# Interface.net
KiCad netlist of a schematic drawn in Altium Designer
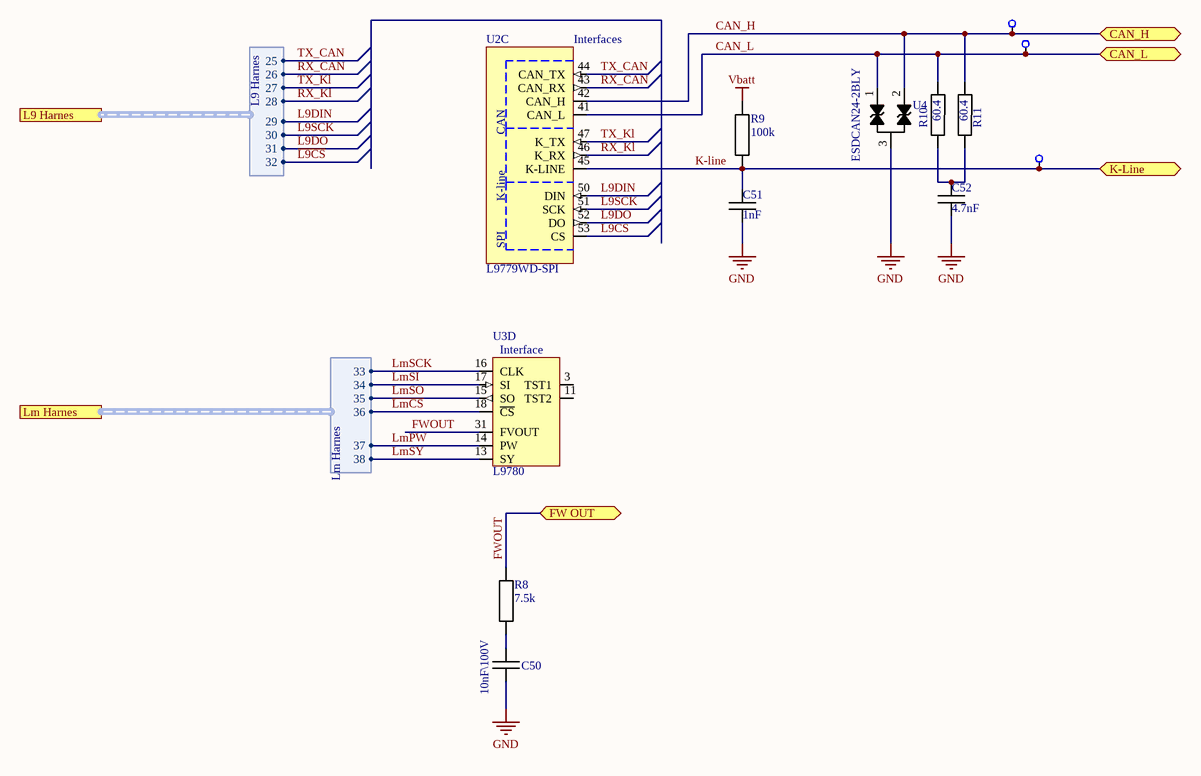
[diagram p0: Interface.SchDoc]

(export (version "E")
  (design (tool "Eeschema 10.0.6"))
  (components
    (comp (ref "C50")
      (value "10n~{F}100V")
      (footprint "SMD 0603")
      (description "CC0603KRX7R0BB103")
      (libsource (lib "Maks_lib") (part "Capasitor"))
    )
    (comp (ref "C51")
      (value "1nF")
      (footprint "SMD 0603")
      (description "CC0603KRX7R9BB102")
      (libsource (lib "Maks_lib") (part "Capasitor"))
    )
    (comp (ref "C52")
      (value "4.7nF")
      (footprint "SMD 0603")
      (description "CC0603KRX7R9BB472")
      (libsource (lib "Maks_lib") (part "Capasitor"))
    )
    (comp (ref "R8")
      (value "7.5k")
      (footprint "SMD 0603")
      (description "RC0603FR-077K5L")
      (libsource (lib "") (part "Resistor_1"))
    )
    (comp (ref "R9")
      (value "100k")
      (footprint "SMD 0603")
      (description "RT0603BRD07100KL")
      (libsource (lib "Maks_lib") (part "Resistor"))
    )
    (comp (ref "R10")
      (value "60.4")
      (footprint "SMD 0603")
      (description "RC0603FR-0760R4L")
      (libsource (lib "Maks_lib") (part "Resistor"))
    )
    (comp (ref "R11")
      (value "60.4")
      (footprint "SMD 0603")
      (description "RC0603FR-0760R4L")
      (libsource (lib "Maks_lib") (part "Resistor"))
    )
    (comp (ref "TP31")
      (value "TestPoint")
      (footprint "TESTPOINT")
      (description "testPoint")
      (libsource (lib "Maks_lib") (part "TestPoint"))
    )
    (comp (ref "TP32")
      (value "TestPoint")
      (footprint "TESTPOINT")
      (description "testPoint")
      (libsource (lib "Maks_lib") (part "TestPoint"))
    )
    (comp (ref "TP33")
      (value "TestPoint")
      (footprint "TESTPOINT")
      (description "testPoint")
      (libsource (lib "Maks_lib") (part "TestPoint"))
    )
    (comp (ref "U2")
      (value "L9779WD-SPI")
      (footprint "HiQUAD-64")
      (description "Multifunction IC for engine management system")
      (libsource (lib "Maks_lib") (part "L9779WD-SPI"))
    )
    (comp (ref "U3")
      (value "L9780")
      (footprint "LQFP-48N")
      (description "Wide range air fuel sensor control interface")
      (libsource (lib "Maks_lib") (part "L9780"))
    )
    (comp (ref "U4")
      (value "ESDCAN24-2BLY")
      (footprint "SOT23")
      (libsource (lib "Maks_lib") (part "ESDCANxx-2BLY"))
    )
  )
  (nets
    (net (code "4") (name "/CAN_H") (class "Default")
      (node (ref "R11") (pin "2") (pinfunction "2_2") (pintype "passive"))
      (node (ref "TP31") (pin "0") (pinfunction "0_0") (pintype "passive"))
      (node (ref "U2") (pin "42") (pinfunction "CAN_H_42") (pintype "bidirectional"))
      (node (ref "U4") (pin "2") (pinfunction "2_2") (pintype "passive"))
    )
    (net (code "5") (name "/CAN_L") (class "Default")
      (node (ref "R10") (pin "2") (pinfunction "2_2") (pintype "passive"))
      (node (ref "TP32") (pin "0") (pinfunction "0_0") (pintype "passive"))
      (node (ref "U2") (pin "41") (pinfunction "CAN_L_41") (pintype "bidirectional"))
      (node (ref "U4") (pin "1") (pinfunction "1_1") (pintype "passive"))
    )
    (net (code "6") (name "/FWOUT") (class "Default")
      (node (ref "R8") (pin "1") (pinfunction "1_1") (pintype "passive"))
      (node (ref "U3") (pin "31") (pinfunction "FVOUT_31") (pintype "passive"))
    )
    (net (code "7") (name "/K-line") (class "Default")
      (node (ref "C51") (pin "2") (pinfunction "2_2") (pintype "passive"))
      (node (ref "R9") (pin "1") (pinfunction "1_1") (pintype "passive"))
      (node (ref "TP33") (pin "0") (pinfunction "0_0") (pintype "passive"))
      (node (ref "U2") (pin "45") (pinfunction "K-LINE_45") (pintype "bidirectional"))
    )
    (net (code "8") (name "/L9CS") (class "Default")
      (node (ref "U2") (pin "53") (pinfunction "CS_53") (pintype "passive"))
    )
    (net (code "9") (name "/L9DIN") (class "Default")
      (node (ref "U2") (pin "50") (pinfunction "DIN_50") (pintype "input"))
    )
    (net (code "10") (name "/L9DO") (class "Default")
      (node (ref "U2") (pin "52") (pinfunction "DO_52") (pintype "output"))
    )
    (net (code "11") (name "/L9SCK") (class "Default")
      (node (ref "U2") (pin "51") (pinfunction "SCK_51") (pintype "input"))
    )
    (net (code "12") (name "/LmCS") (class "Default")
      (node (ref "U3") (pin "18") (pinfunction "CS_18") (pintype "passive"))
    )
    (net (code "13") (name "/LmPW") (class "Default")
      (node (ref "U3") (pin "14") (pinfunction "PW_14") (pintype "passive"))
    )
    (net (code "14") (name "/LmSCK") (class "Default")
      (node (ref "U3") (pin "16") (pinfunction "CLK_16") (pintype "passive"))
    )
    (net (code "15") (name "/LmSI") (class "Default")
      (node (ref "U3") (pin "17") (pinfunction "SI_17") (pintype "input"))
    )
    (net (code "16") (name "/LmSO") (class "Default")
      (node (ref "U3") (pin "15") (pinfunction "SO_15") (pintype "output"))
    )
    (net (code "17") (name "/LmSY") (class "Default")
      (node (ref "U3") (pin "13") (pinfunction "SY_13") (pintype "passive"))
    )
    (net (code "18") (name "/RX_CAN") (class "Default")
      (node (ref "U2") (pin "43") (pinfunction "CAN_RX_43") (pintype "output"))
    )
    (net (code "19") (name "/RX_Kl") (class "Default")
      (node (ref "U2") (pin "46") (pinfunction "K_RX_46") (pintype "output"))
    )
    (net (code "20") (name "/TX_CAN") (class "Default")
      (node (ref "U2") (pin "44") (pinfunction "CAN_TX_44") (pintype "input"))
    )
    (net (code "21") (name "/TX_Kl") (class "Default")
      (node (ref "U2") (pin "47") (pinfunction "K_TX_47") (pintype "input"))
    )
    (net (code "24") (name "GND") (class "Default")
      (node (ref "C50") (pin "1") (pinfunction "1_1") (pintype "passive"))
      (node (ref "C51") (pin "1") (pinfunction "1_1") (pintype "passive"))
      (node (ref "C52") (pin "1") (pinfunction "1_1") (pintype "passive"))
      (node (ref "U4") (pin "3") (pinfunction "3_3") (pintype "passive"))
    )
    (net (code "25") (name "Net-(C50-Pad2)") (class "Default")
      (node (ref "C50") (pin "2") (pinfunction "2_2") (pintype "passive"))
      (node (ref "R8") (pin "2") (pinfunction "2_2") (pintype "passive"))
    )
    (net (code "26") (name "Net-(C52-Pad2)") (class "Default")
      (node (ref "C52") (pin "2") (pinfunction "2_2") (pintype "passive"))
      (node (ref "R10") (pin "1") (pinfunction "1_1") (pintype "passive"))
      (node (ref "R11") (pin "1") (pinfunction "1_1") (pintype "passive"))
    )
    (net (code "27") (name "Vbatt") (class "Default")
      (node (ref "R9") (pin "2") (pinfunction "2_2") (pintype "passive"))
    )
    (net (code "28") (name "unconnected-(U3D-TST1-Pad3)") (class "Default")
      (node (ref "U3") (pin "3") (pinfunction "TST1_3") (pintype "passive"))
    )
    (net (code "29") (name "unconnected-(U3D-TST2-Pad11)") (class "Default")
      (node (ref "U3") (pin "11") (pinfunction "TST2_11") (pintype "passive"))
    )
  )
)
